# multiwii-conn.net
KiCad netlist of a schematic drawn in EAGLE
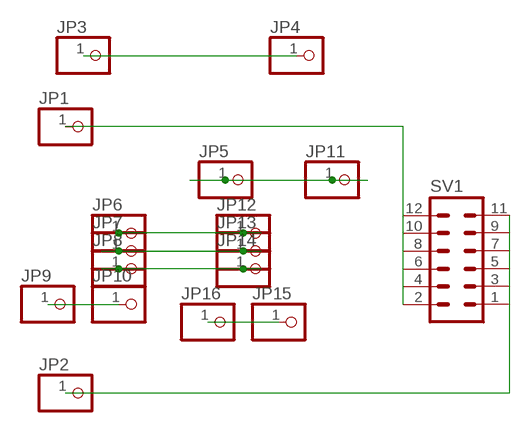
[diagram p0: schematic, sheet 1]

(export (version "E")
  (design (tool "Eeschema 10.0.6"))
  (components
    (comp (ref "JP1")
      (value "PINHD-1X1")
      (footprint "eagle-import:1X01")
      (libsource (lib "eagle-import") (part "PINHD-1X1"))
    )
    (comp (ref "JP2")
      (value "PINHD-1X1")
      (footprint "eagle-import:1X01")
      (libsource (lib "eagle-import") (part "PINHD-1X1"))
    )
    (comp (ref "JP3")
      (value "PINHD-1X1")
      (footprint "eagle-import:1X01")
      (libsource (lib "eagle-import") (part "PINHD-1X1"))
    )
    (comp (ref "JP4")
      (value "PINHD-1X1")
      (footprint "eagle-import:1X01")
      (libsource (lib "eagle-import") (part "PINHD-1X1"))
    )
    (comp (ref "JP5")
      (value "PINHD-1X1")
      (footprint "eagle-import:1X01")
      (libsource (lib "eagle-import") (part "PINHD-1X1"))
    )
    (comp (ref "JP6")
      (value "PINHD-1X1")
      (footprint "eagle-import:1X01")
      (libsource (lib "eagle-import") (part "PINHD-1X1"))
    )
    (comp (ref "JP7")
      (value "PINHD-1X1")
      (footprint "eagle-import:1X01")
      (libsource (lib "eagle-import") (part "PINHD-1X1"))
    )
    (comp (ref "JP8")
      (value "PINHD-1X1")
      (footprint "eagle-import:1X01")
      (libsource (lib "eagle-import") (part "PINHD-1X1"))
    )
    (comp (ref "JP9")
      (value "PINHD-1X1")
      (footprint "eagle-import:1X01")
      (libsource (lib "eagle-import") (part "PINHD-1X1"))
    )
    (comp (ref "JP10")
      (value "PINHD-1X1")
      (footprint "eagle-import:1X01")
      (libsource (lib "eagle-import") (part "PINHD-1X1"))
    )
    (comp (ref "JP11")
      (value "PINHD-1X1")
      (footprint "eagle-import:1X01")
      (libsource (lib "eagle-import") (part "PINHD-1X1"))
    )
    (comp (ref "JP12")
      (value "PINHD-1X1")
      (footprint "eagle-import:1X01")
      (libsource (lib "eagle-import") (part "PINHD-1X1"))
    )
    (comp (ref "JP13")
      (value "PINHD-1X1")
      (footprint "eagle-import:1X01")
      (libsource (lib "eagle-import") (part "PINHD-1X1"))
    )
    (comp (ref "JP14")
      (value "PINHD-1X1")
      (footprint "eagle-import:1X01")
      (libsource (lib "eagle-import") (part "PINHD-1X1"))
    )
    (comp (ref "JP15")
      (value "PINHD-1X1")
      (footprint "eagle-import:1X01")
      (libsource (lib "eagle-import") (part "PINHD-1X1"))
    )
    (comp (ref "JP16")
      (value "PINHD-1X1")
      (footprint "eagle-import:1X01")
      (libsource (lib "eagle-import") (part "PINHD-1X1"))
    )
    (comp (ref "SV1")
      (value "MA06-2")
      (footprint "eagle-import:MA06-2")
      (libsource (lib "eagle-import") (part "MA06-2"))
    )
  )
  (nets
    (net (code "1") (name "Net-(JP1-Pad1)") (class "Default")
      (node (ref "JP1") (pin "1") (pinfunction "1_1") (pintype "passive"))
      (node (ref "SV1") (pin "10") (pinfunction "10_10") (pintype "passive"))
      (node (ref "SV1") (pin "12") (pinfunction "12_12") (pintype "passive"))
      (node (ref "SV1") (pin "2") (pinfunction "2_2") (pintype "passive"))
      (node (ref "SV1") (pin "4") (pinfunction "4_4") (pintype "passive"))
      (node (ref "SV1") (pin "6") (pinfunction "6_6") (pintype "passive"))
      (node (ref "SV1") (pin "8") (pinfunction "8_8") (pintype "passive"))
    )
    (net (code "2") (name "Net-(JP2-Pad1)") (class "Default")
      (node (ref "JP2") (pin "1") (pinfunction "1_1") (pintype "passive"))
      (node (ref "SV1") (pin "1") (pinfunction "1_1") (pintype "passive"))
      (node (ref "SV1") (pin "11") (pinfunction "11_11") (pintype "passive"))
      (node (ref "SV1") (pin "3") (pinfunction "3_3") (pintype "passive"))
      (node (ref "SV1") (pin "5") (pinfunction "5_5") (pintype "passive"))
      (node (ref "SV1") (pin "7") (pinfunction "7_7") (pintype "passive"))
      (node (ref "SV1") (pin "9") (pinfunction "9_9") (pintype "passive"))
    )
    (net (code "3") (name "Net-(JP3-Pad1)") (class "Default")
      (node (ref "JP3") (pin "1") (pinfunction "1_1") (pintype "passive"))
      (node (ref "JP4") (pin "1") (pinfunction "1_1") (pintype "passive"))
    )
    (net (code "4") (name "Net-(JP10-Pad1)") (class "Default")
      (node (ref "JP10") (pin "1") (pinfunction "1_1") (pintype "passive"))
      (node (ref "JP9") (pin "1") (pinfunction "1_1") (pintype "passive"))
    )
    (net (code "5") (name "Net-(JP11-Pad1)") (class "Default")
      (node (ref "JP11") (pin "1") (pinfunction "1_1") (pintype "passive"))
      (node (ref "JP5") (pin "1") (pinfunction "1_1") (pintype "passive"))
    )
    (net (code "6") (name "Net-(JP12-Pad1)") (class "Default")
      (node (ref "JP12") (pin "1") (pinfunction "1_1") (pintype "passive"))
      (node (ref "JP6") (pin "1") (pinfunction "1_1") (pintype "passive"))
    )
    (net (code "7") (name "Net-(JP13-Pad1)") (class "Default")
      (node (ref "JP13") (pin "1") (pinfunction "1_1") (pintype "passive"))
      (node (ref "JP7") (pin "1") (pinfunction "1_1") (pintype "passive"))
    )
    (net (code "8") (name "Net-(JP14-Pad1)") (class "Default")
      (node (ref "JP14") (pin "1") (pinfunction "1_1") (pintype "passive"))
      (node (ref "JP8") (pin "1") (pinfunction "1_1") (pintype "passive"))
    )
    (net (code "9") (name "Net-(JP15-Pad1)") (class "Default")
      (node (ref "JP15") (pin "1") (pinfunction "1_1") (pintype "passive"))
      (node (ref "JP16") (pin "1") (pinfunction "1_1") (pintype "passive"))
    )
  )
)
